# 05_DATA_IO.net
KiCad netlist of a schematic drawn in Altium Designer
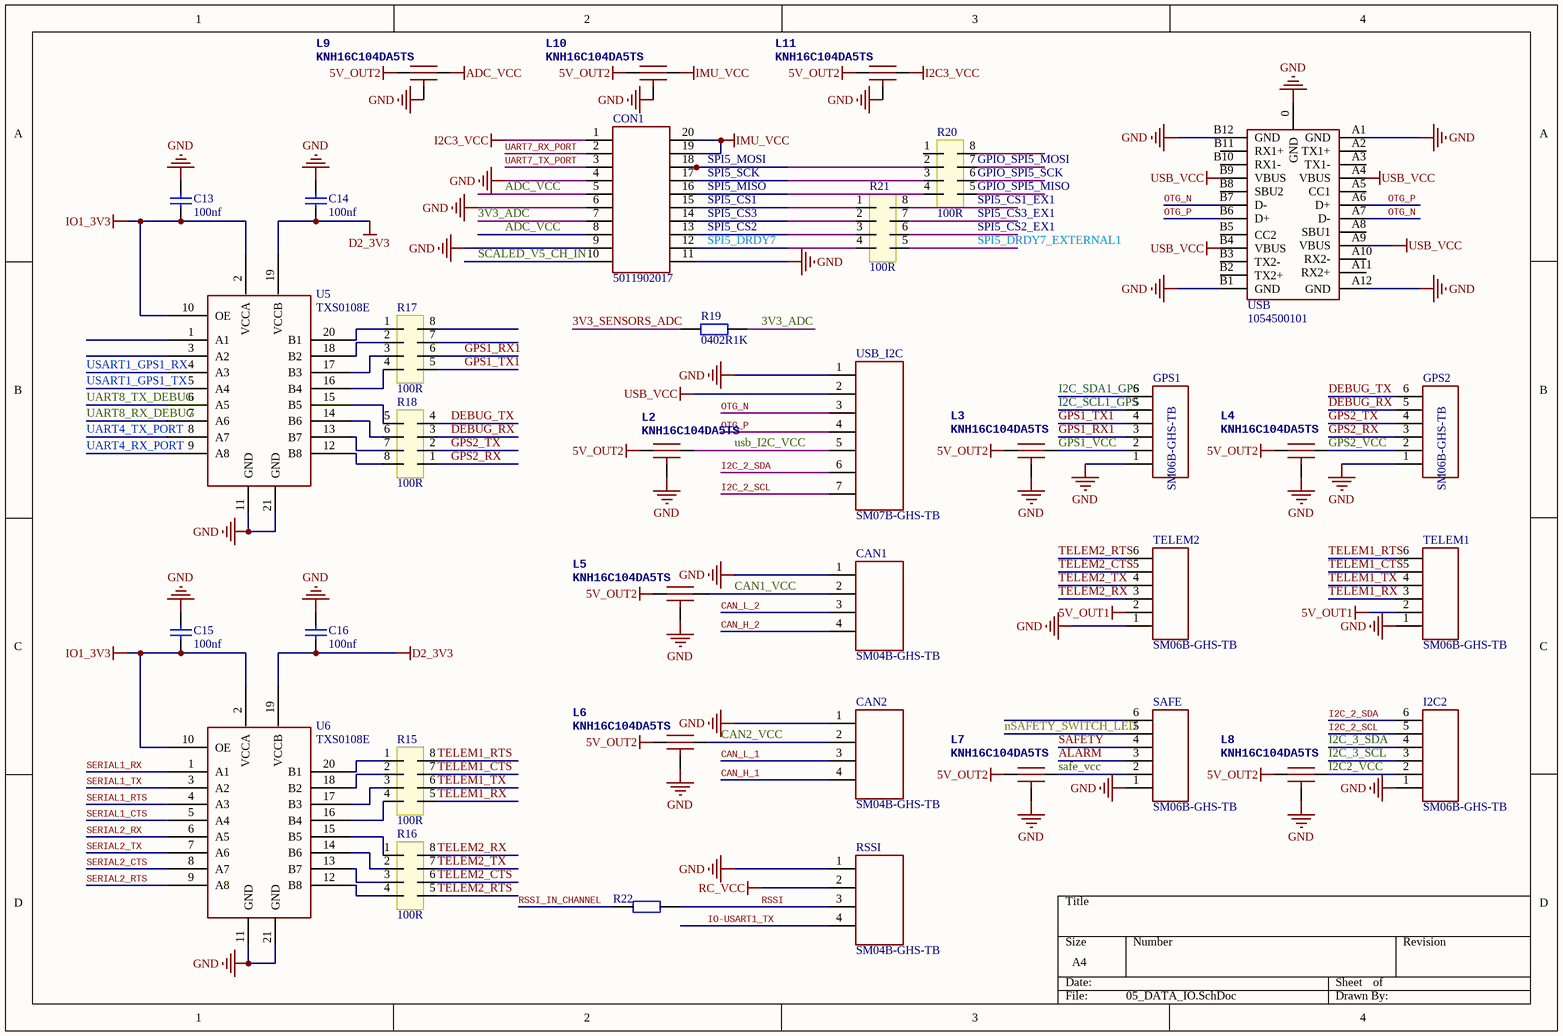
[diagram p0: 05_DATA_IO.SchDoc]

(export (version "E")
  (design (tool "Eeschema 10.0.6"))
  (components
    (comp (ref "C13") (value "100nf") (libsource (lib "Miscellaneous Devices") (part "Cap")))
    (comp (ref "C14") (value "100nf") (libsource (lib "Miscellaneous Devices") (part "Cap")))
    (comp (ref "C15") (value "100nf") (libsource (lib "Miscellaneous Devices") (part "Cap")))
    (comp (ref "C16") (value "100nf") (libsource (lib "Miscellaneous Devices") (part "Cap")))
    (comp (ref "CAN1")
      (value "SM04B-GHS-TB")
      (footprint "BM04B-GHS")
      (libsource (lib "CUAV") (part "SM04B-GHS-TB"))
    )
    (comp (ref "CAN2")
      (value "SM04B-GHS-TB")
      (footprint "BM04B-GHS")
      (libsource (lib "CUAV") (part "SM04B-GHS-TB"))
    )
    (comp (ref "CON1")
      (value "5011902017")
      (footprint "5011902017")
      (libsource (lib "CUAV") (part "5011902017"))
    )
    (comp (ref "GPS1")
      (value "SM06B-GHS-TB")
      (footprint "SM06B-GHS-TB")
      (libsource (lib "CUAV") (part "SM06B-GHS-TB"))
    )
    (comp (ref "GPS2")
      (value "SM06B-GHS-TB")
      (footprint "SM06B-GHS-TB")
      (libsource (lib "CUAV") (part "SM06B-GHS-TB"))
    )
    (comp (ref "I2C2")
      (value "SM06B-GHS-TB")
      (footprint "SM06B-GHS-TB")
      (libsource (lib "CUAV") (part "SM06B-GHS-TB"))
    )
    (comp (ref "L2")
      (value "KNH16C104DA5TS")
      (footprint "KYOCERA-KNH16-DA")
      (description "Capacitor, Filter, 0.1uF, 25V, 2A, 0603, SMD")
      (fields (field (name "3DR_PARTNO") "ECM0719"))
      (libsource (lib "PCA_0005_FULL_CB_REV_A") (part "KNH16C104DA5TS"))
    )
    (comp (ref "L3")
      (value "KNH16C104DA5TS")
      (footprint "KYOCERA-KNH16-DA")
      (description "Capacitor, Filter, 0.1uF, 25V, 2A, 0603, SMD")
      (fields (field (name "3DR_PARTNO") "ECM0719"))
      (libsource (lib "PCA_0005_FULL_CB_REV_A") (part "KNH16C104DA5TS"))
    )
    (comp (ref "L4")
      (value "KNH16C104DA5TS")
      (footprint "KYOCERA-KNH16-DA")
      (description "Capacitor, Filter, 0.1uF, 25V, 2A, 0603, SMD")
      (fields (field (name "3DR_PARTNO") "ECM0719"))
      (libsource (lib "PCA_0005_FULL_CB_REV_A") (part "KNH16C104DA5TS"))
    )
    (comp (ref "L5")
      (value "KNH16C104DA5TS")
      (footprint "KYOCERA-KNH16-DA")
      (description "Capacitor, Filter, 0.1uF, 25V, 2A, 0603, SMD")
      (fields (field (name "3DR_PARTNO") "ECM0719"))
      (libsource (lib "PCA_0005_FULL_CB_REV_A") (part "KNH16C104DA5TS"))
    )
    (comp (ref "L6")
      (value "KNH16C104DA5TS")
      (footprint "KYOCERA-KNH16-DA")
      (description "Capacitor, Filter, 0.1uF, 25V, 2A, 0603, SMD")
      (fields (field (name "3DR_PARTNO") "ECM0719"))
      (libsource (lib "PCA_0005_FULL_CB_REV_A") (part "KNH16C104DA5TS"))
    )
    (comp (ref "L7")
      (value "KNH16C104DA5TS")
      (footprint "KYOCERA-KNH16-DA")
      (description "Capacitor, Filter, 0.1uF, 25V, 2A, 0603, SMD")
      (fields (field (name "3DR_PARTNO") "ECM0719"))
      (libsource (lib "PCA_0005_FULL_CB_REV_A") (part "KNH16C104DA5TS"))
    )
    (comp (ref "L8")
      (value "KNH16C104DA5TS")
      (footprint "KYOCERA-KNH16-DA")
      (description "Capacitor, Filter, 0.1uF, 25V, 2A, 0603, SMD")
      (fields (field (name "3DR_PARTNO") "ECM0719"))
      (libsource (lib "PCA_0005_FULL_CB_REV_A") (part "KNH16C104DA5TS"))
    )
    (comp (ref "L9")
      (value "KNH16C104DA5TS")
      (footprint "KYOCERA-KNH16-DA")
      (description "Capacitor, Filter, 0.1uF, 25V, 2A, 0603, SMD")
      (fields (field (name "3DR_PARTNO") "ECM0719"))
      (libsource (lib "PCA_0005_FULL_CB_REV_A") (part "KNH16C104DA5TS"))
    )
    (comp (ref "L10")
      (value "KNH16C104DA5TS")
      (footprint "KYOCERA-KNH16-DA")
      (description "Capacitor, Filter, 0.1uF, 25V, 2A, 0603, SMD")
      (fields (field (name "3DR_PARTNO") "ECM0719"))
      (libsource (lib "PCA_0005_FULL_CB_REV_A") (part "KNH16C104DA5TS"))
    )
    (comp (ref "L11")
      (value "KNH16C104DA5TS")
      (footprint "KYOCERA-KNH16-DA")
      (description "Capacitor, Filter, 0.1uF, 25V, 2A, 0603, SMD")
      (fields (field (name "3DR_PARTNO") "ECM0719"))
      (libsource (lib "PCA_0005_FULL_CB_REV_A") (part "KNH16C104DA5TS"))
    )
    (comp (ref "R15") (value "100R") (footprint "0402_4r") (libsource (lib "CUAV") (part "0402-8R-4R")))
    (comp (ref "R16") (value "100R") (footprint "0402_4r") (libsource (lib "CUAV") (part "0402-8R-4R")))
    (comp (ref "R17") (value "100R") (footprint "0402_4r") (libsource (lib "CUAV") (part "0402-8R-4R")))
    (comp (ref "R18") (value "100R") (footprint "0402_4r") (libsource (lib "") (part "0402-8R-4R_1")))
    (comp (ref "R19")
      (value "0402R1K")
      (footprint "0402R")
      (description "0402R1K 1%")
      (libsource (lib "CUAV") (part "0402R1K"))
    )
    (comp (ref "R20") (value "100R") (footprint "0402_4r") (libsource (lib "CUAV") (part "0402-8R-4R")))
    (comp (ref "R21") (value "100R") (footprint "0402_4r") (libsource (lib "CUAV") (part "0402-8R-4R")))
    (comp (ref "R22")
      (value "0402R100R")
      (footprint "0402R")
      (description "0402R100R 1%")
      (libsource (lib "CUAV") (part "0402R100R"))
    )
    (comp (ref "RSSI")
      (value "SM04B-GHS-TB")
      (footprint "BM04B-GHS")
      (libsource (lib "CUAV") (part "SM04B-GHS-TB"))
    )
    (comp (ref "SAFE")
      (value "SM06B-GHS-TB")
      (footprint "SM06B-GHS-TB")
      (libsource (lib "CUAV") (part "SM06B-GHS-TB"))
    )
    (comp (ref "TELEM1")
      (value "SM06B-GHS-TB")
      (footprint "SM06B-GHS-TB")
      (libsource (lib "CUAV") (part "SM06B-GHS-TB"))
    )
    (comp (ref "TELEM2")
      (value "SM06B-GHS-TB")
      (footprint "SM06B-GHS-TB")
      (libsource (lib "CUAV") (part "SM06B-GHS-TB"))
    )
    (comp (ref "U5") (value "TXS0108E") (footprint "VQFN20") (libsource (lib "CUAV") (part "TXS0108E")))
    (comp (ref "U6") (value "TXS0108E") (footprint "VQFN20") (libsource (lib "CUAV") (part "TXS0108E")))
    (comp (ref "USB")
      (value "1054500101")
      (footprint "1054500101")
      (libsource (lib "CUAV") (part "1054500101"))
    )
    (comp (ref "USB_I2C")
      (value "SM07B-GHS-TB")
      (footprint "SM07B-GHS-TB")
      (libsource (lib "CUAV") (part "SM07B-GHS-TB"))
    )
  )
  (nets
    (net (code "1") (name "/3V3_ADC") (class "Default")
      (node (ref "CON1") (pin "7") (pintype "passive"))
      (node (ref "R19") (pin "2") (pintype "passive"))
    )
    (net (code "2") (name "/3V3_SENSORS_ADC") (class "Default")
      (node (ref "R19") (pin "1") (pintype "passive"))
    )
    (net (code "3") (name "/ALARM") (class "Default") (node (ref "SAFE") (pin "3") (pintype "passive")))
    (net (code "4") (name "/CAN1_VCC") (class "Default")
      (node (ref "CAN1") (pin "2") (pintype "passive"))
      (node (ref "L5") (pin "P$2") (pinfunction "P$2_P$2") (pintype "passive"))
    )
    (net (code "5") (name "/CAN2_VCC") (class "Default")
      (node (ref "CAN2") (pin "2") (pintype "passive"))
      (node (ref "L6") (pin "P$2") (pinfunction "P$2_P$2") (pintype "passive"))
    )
    (net (code "6") (name "/CAN_H_1") (class "Default") (node (ref "CAN2") (pin "4") (pintype "passive")))
    (net (code "7") (name "/CAN_H_2") (class "Default") (node (ref "CAN1") (pin "4") (pintype "passive")))
    (net (code "8") (name "/CAN_L_1") (class "Default") (node (ref "CAN2") (pin "3") (pintype "passive")))
    (net (code "9") (name "/CAN_L_2") (class "Default") (node (ref "CAN1") (pin "3") (pintype "passive")))
    (net (code "10") (name "/DEBUG_RX") (class "Default")
      (node (ref "GPS2") (pin "5") (pintype "passive"))
      (node (ref "R18") (pin "3") (pinfunction "3_3") (pintype "passive"))
    )
    (net (code "11") (name "/DEBUG_TX") (class "Default")
      (node (ref "GPS2") (pin "6") (pintype "passive"))
      (node (ref "R18") (pin "4") (pinfunction "4_4") (pintype "passive"))
    )
    (net (code "12") (name "/GPIO_SPI5_MISO") (class "Default")
      (node (ref "R20") (pin "5") (pinfunction "5_5") (pintype "passive"))
    )
    (net (code "13") (name "/GPIO_SPI5_MOSI") (class "Default")
      (node (ref "R20") (pin "7") (pinfunction "7_7") (pintype "passive"))
    )
    (net (code "14") (name "/GPIO_SPI5_SCK") (class "Default")
      (node (ref "R20") (pin "6") (pinfunction "6_6") (pintype "passive"))
    )
    (net (code "15") (name "/GPS1_RX1") (class "Default")
      (node (ref "GPS1") (pin "3") (pintype "passive"))
      (node (ref "R17") (pin "6") (pinfunction "6_6") (pintype "passive"))
    )
    (net (code "16") (name "/GPS1_TX1") (class "Default")
      (node (ref "GPS1") (pin "4") (pintype "passive"))
      (node (ref "R17") (pin "5") (pinfunction "5_5") (pintype "passive"))
    )
    (net (code "17") (name "/GPS1_VCC") (class "Default")
      (node (ref "GPS1") (pin "2") (pintype "passive"))
      (node (ref "L3") (pin "P$2") (pinfunction "P$2_P$2") (pintype "passive"))
    )
    (net (code "18") (name "/GPS2_RX") (class "Default")
      (node (ref "GPS2") (pin "3") (pintype "passive"))
      (node (ref "R18") (pin "1") (pinfunction "1_1") (pintype "passive"))
    )
    (net (code "19") (name "/GPS2_TX") (class "Default")
      (node (ref "GPS2") (pin "4") (pintype "passive"))
      (node (ref "R18") (pin "2") (pinfunction "2_2") (pintype "passive"))
    )
    (net (code "20") (name "/GPS2_VCC") (class "Default")
      (node (ref "GPS2") (pin "2") (pintype "passive"))
      (node (ref "L4") (pin "P$2") (pinfunction "P$2_P$2") (pintype "passive"))
    )
    (net (code "21") (name "/I2C2_VCC") (class "Default")
      (node (ref "I2C2") (pin "2") (pintype "passive"))
      (node (ref "L8") (pin "P$2") (pinfunction "P$2_P$2") (pintype "passive"))
    )
    (net (code "22") (name "/I2C_2_SCL") (class "Default")
      (node (ref "I2C2") (pin "5") (pintype "passive"))
      (node (ref "USB_I2C") (pin "7") (pintype "passive"))
    )
    (net (code "23") (name "/I2C_2_SDA") (class "Default")
      (node (ref "I2C2") (pin "6") (pintype "passive"))
      (node (ref "USB_I2C") (pin "6") (pintype "passive"))
    )
    (net (code "24") (name "/I2C_3_SCL") (class "Default") (node (ref "I2C2") (pin "3") (pintype "passive")))
    (net (code "25") (name "/I2C_3_SDA") (class "Default") (node (ref "I2C2") (pin "4") (pintype "passive")))
    (net (code "26") (name "/I2C_SCL1_GPS") (class "Default")
      (node (ref "GPS1") (pin "5") (pintype "passive"))
    )
    (net (code "27") (name "/I2C_SDA1_GPS") (class "Default")
      (node (ref "GPS1") (pin "6") (pintype "passive"))
    )
    (net (code "28") (name "/IO-USART1_TX") (class "Default")
      (node (ref "RSSI") (pin "4") (pintype "passive"))
    )
    (net (code "29") (name "/OTG_N") (class "Default")
      (node (ref "USB") (pin "A7") (pinfunction "D-_A7") (pintype "passive"))
      (node (ref "USB") (pin "B7") (pinfunction "D-_B7") (pintype "passive"))
      (node (ref "USB_I2C") (pin "3") (pintype "passive"))
    )
    (net (code "30") (name "/OTG_P") (class "Default")
      (node (ref "USB") (pin "A6") (pinfunction "D+_A6") (pintype "passive"))
      (node (ref "USB") (pin "B6") (pinfunction "D+_B6") (pintype "passive"))
      (node (ref "USB_I2C") (pin "4") (pintype "passive"))
    )
    (net (code "31") (name "/RSSI") (class "Default")
      (node (ref "R22") (pin "2") (pintype "passive"))
      (node (ref "RSSI") (pin "3") (pintype "passive"))
    )
    (net (code "32") (name "/RSSI_IN_CHANNEL") (class "Default")
      (node (ref "R22") (pin "1") (pintype "passive"))
    )
    (net (code "33") (name "/SAFETY") (class "Default") (node (ref "SAFE") (pin "4") (pintype "passive")))
    (net (code "34") (name "/SCALED_V5_CH_IN") (class "Default")
      (node (ref "CON1") (pin "10") (pintype "passive"))
    )
    (net (code "35") (name "/SERIAL1_CTS") (class "Default")
      (node (ref "U6") (pin "5") (pinfunction "A4_5") (pintype "passive"))
    )
    (net (code "36") (name "/SERIAL1_RTS") (class "Default")
      (node (ref "U6") (pin "4") (pinfunction "A3_4") (pintype "passive"))
    )
    (net (code "37") (name "/SERIAL1_RX") (class "Default")
      (node (ref "U6") (pin "1") (pinfunction "A1_1") (pintype "passive"))
    )
    (net (code "38") (name "/SERIAL1_TX") (class "Default")
      (node (ref "U6") (pin "3") (pinfunction "A2_3") (pintype "passive"))
    )
    (net (code "39") (name "/SERIAL2_CTS") (class "Default")
      (node (ref "U6") (pin "8") (pinfunction "A7_8") (pintype "passive"))
    )
    (net (code "40") (name "/SERIAL2_RTS") (class "Default")
      (node (ref "U6") (pin "9") (pinfunction "A8_9") (pintype "passive"))
    )
    (net (code "41") (name "/SERIAL2_RX") (class "Default")
      (node (ref "U6") (pin "6") (pinfunction "A5_6") (pintype "passive"))
    )
    (net (code "42") (name "/SERIAL2_TX") (class "Default")
      (node (ref "U6") (pin "7") (pinfunction "A6_7") (pintype "passive"))
    )
    (net (code "43") (name "/SPI5_CS1") (class "Default")
      (node (ref "CON1") (pin "15") (pintype "passive"))
      (node (ref "R21") (pin "1") (pinfunction "1_1") (pintype "passive"))
    )
    (net (code "44") (name "/SPI5_CS1_EX1") (class "Default")
      (node (ref "R21") (pin "8") (pinfunction "8_8") (pintype "passive"))
    )
    (net (code "45") (name "/SPI5_CS2") (class "Default")
      (node (ref "CON1") (pin "13") (pintype "passive"))
      (node (ref "R21") (pin "3") (pinfunction "3_3") (pintype "passive"))
    )
    (net (code "46") (name "/SPI5_CS2_EX1") (class "Default")
      (node (ref "R21") (pin "6") (pinfunction "6_6") (pintype "passive"))
    )
    (net (code "47") (name "/SPI5_CS3") (class "Default")
      (node (ref "CON1") (pin "14") (pintype "passive"))
      (node (ref "R21") (pin "2") (pinfunction "2_2") (pintype "passive"))
    )
    (net (code "48") (name "/SPI5_CS3_EX1") (class "Default")
      (node (ref "R21") (pin "7") (pinfunction "7_7") (pintype "passive"))
    )
    (net (code "49") (name "/SPI5_DRDY7") (class "Default")
      (node (ref "CON1") (pin "12") (pintype "passive"))
      (node (ref "R21") (pin "4") (pinfunction "4_4") (pintype "passive"))
    )
    (net (code "50") (name "/SPI5_DRDY7_EXTERNAL1") (class "Default")
      (node (ref "R21") (pin "5") (pinfunction "5_5") (pintype "passive"))
    )
    (net (code "51") (name "/SPI5_MISO") (class "Default")
      (node (ref "CON1") (pin "16") (pintype "passive"))
      (node (ref "R20") (pin "4") (pinfunction "4_4") (pintype "passive"))
    )
    (net (code "52") (name "/SPI5_MOSI") (class "Default")
      (node (ref "CON1") (pin "18") (pintype "passive"))
      (node (ref "R20") (pin "2") (pinfunction "2_2") (pintype "passive"))
    )
    (net (code "53") (name "/SPI5_SCK") (class "Default")
      (node (ref "CON1") (pin "17") (pintype "passive"))
      (node (ref "R20") (pin "3") (pinfunction "3_3") (pintype "passive"))
    )
    (net (code "54") (name "/TELEM1_CTS") (class "Default")
      (node (ref "R15") (pin "7") (pinfunction "7_7") (pintype "passive"))
      (node (ref "TELEM1") (pin "5") (pintype "passive"))
    )
    (net (code "55") (name "/TELEM1_RTS") (class "Default")
      (node (ref "R15") (pin "8") (pinfunction "8_8") (pintype "passive"))
      (node (ref "TELEM1") (pin "6") (pintype "passive"))
    )
    (net (code "56") (name "/TELEM1_RX") (class "Default")
      (node (ref "R15") (pin "5") (pinfunction "5_5") (pintype "passive"))
      (node (ref "TELEM1") (pin "3") (pintype "passive"))
    )
    (net (code "57") (name "/TELEM1_TX") (class "Default")
      (node (ref "R15") (pin "6") (pinfunction "6_6") (pintype "passive"))
      (node (ref "TELEM1") (pin "4") (pintype "passive"))
    )
    (net (code "58") (name "/TELEM2_CTS") (class "Default")
      (node (ref "R16") (pin "6") (pinfunction "6_6") (pintype "passive"))
      (node (ref "TELEM2") (pin "5") (pintype "passive"))
    )
    (net (code "59") (name "/TELEM2_RTS") (class "Default")
      (node (ref "R16") (pin "5") (pinfunction "5_5") (pintype "passive"))
      (node (ref "TELEM2") (pin "6") (pintype "passive"))
    )
    (net (code "60") (name "/TELEM2_RX") (class "Default")
      (node (ref "R16") (pin "8") (pinfunction "8_8") (pintype "passive"))
      (node (ref "TELEM2") (pin "3") (pintype "passive"))
    )
    (net (code "61") (name "/TELEM2_TX") (class "Default")
      (node (ref "R16") (pin "7") (pinfunction "7_7") (pintype "passive"))
      (node (ref "TELEM2") (pin "4") (pintype "passive"))
    )
    (net (code "62") (name "/UART4_RX_PORT") (class "Default")
      (node (ref "U5") (pin "9") (pinfunction "A8_9") (pintype "passive"))
    )
    (net (code "63") (name "/UART4_TX_PORT") (class "Default")
      (node (ref "U5") (pin "8") (pinfunction "A7_8") (pintype "passive"))
    )
    (net (code "64") (name "/UART7_RX_PORT") (class "Default")
      (node (ref "CON1") (pin "2") (pintype "passive"))
    )
    (net (code "65") (name "/UART7_TX_PORT") (class "Default")
      (node (ref "CON1") (pin "3") (pintype "passive"))
    )
    (net (code "66") (name "/UART8_RX_DEBUG") (class "Default")
      (node (ref "U5") (pin "7") (pinfunction "A6_7") (pintype "passive"))
    )
    (net (code "67") (name "/UART8_TX_DEBUG") (class "Default")
      (node (ref "U5") (pin "6") (pinfunction "A5_6") (pintype "passive"))
    )
    (net (code "68") (name "/USART1_GPS1_RX") (class "Default")
      (node (ref "U5") (pin "4") (pinfunction "A3_4") (pintype "passive"))
    )
    (net (code "69") (name "/USART1_GPS1_TX") (class "Default")
      (node (ref "U5") (pin "5") (pinfunction "A4_5") (pintype "passive"))
    )
    (net (code "70") (name "/nSAFETY_SWITCH_LED") (class "Default")
      (node (ref "SAFE") (pin "5") (pintype "passive"))
    )
    (net (code "71") (name "/safe_vcc") (class "Default")
      (node (ref "L7") (pin "P$2") (pinfunction "P$2_P$2") (pintype "passive"))
      (node (ref "SAFE") (pin "2") (pintype "passive"))
    )
    (net (code "72") (name "/usb_I2C_VCC") (class "Default")
      (node (ref "L2") (pin "P$2") (pinfunction "P$2_P$2") (pintype "passive"))
      (node (ref "USB_I2C") (pin "5") (pintype "passive"))
    )
    (net (code "73") (name "5V_OUT1") (class "Default")
      (node (ref "TELEM1") (pin "2") (pintype "passive"))
      (node (ref "TELEM2") (pin "2") (pintype "passive"))
    )
    (net (code "74") (name "5V_OUT2") (class "Default")
      (node (ref "L10") (pin "P$1") (pinfunction "P$1_P$1") (pintype "passive"))
      (node (ref "L11") (pin "P$1") (pinfunction "P$1_P$1") (pintype "passive"))
      (node (ref "L2") (pin "P$1") (pinfunction "P$1_P$1") (pintype "passive"))
      (node (ref "L3") (pin "P$1") (pinfunction "P$1_P$1") (pintype "passive"))
      (node (ref "L4") (pin "P$1") (pinfunction "P$1_P$1") (pintype "passive"))
      (node (ref "L5") (pin "P$1") (pinfunction "P$1_P$1") (pintype "passive"))
      (node (ref "L6") (pin "P$1") (pinfunction "P$1_P$1") (pintype "passive"))
      (node (ref "L7") (pin "P$1") (pinfunction "P$1_P$1") (pintype "passive"))
      (node (ref "L8") (pin "P$1") (pinfunction "P$1_P$1") (pintype "passive"))
      (node (ref "L9") (pin "P$1") (pinfunction "P$1_P$1") (pintype "passive"))
    )
    (net (code "75") (name "ADC_VCC") (class "Default")
      (node (ref "CON1") (pin "5") (pintype "passive"))
      (node (ref "CON1") (pin "8") (pintype "passive"))
      (node (ref "L9") (pin "P$2") (pinfunction "P$2_P$2") (pintype "passive"))
    )
    (net (code "76") (name "D2_3V3") (class "Default")
      (node (ref "C14") (pin "2") (pinfunction "2_2") (pintype "passive"))
      (node (ref "C16") (pin "2") (pinfunction "2_2") (pintype "passive"))
      (node (ref "U5") (pin "19") (pinfunction "VCCB_19") (pintype "passive"))
      (node (ref "U6") (pin "19") (pinfunction "VCCB_19") (pintype "passive"))
    )
    (net (code "77") (name "GND") (class "Default")
      (node (ref "C13") (pin "1") (pinfunction "1_1") (pintype "passive"))
      (node (ref "C14") (pin "1") (pinfunction "1_1") (pintype "passive"))
      (node (ref "C15") (pin "1") (pinfunction "1_1") (pintype "passive"))
      (node (ref "C16") (pin "1") (pinfunction "1_1") (pintype "passive"))
      (node (ref "CAN1") (pin "1") (pintype "passive"))
      (node (ref "CAN2") (pin "1") (pintype "passive"))
      (node (ref "CON1") (pin "11") (pintype "passive"))
      (node (ref "CON1") (pin "4") (pintype "passive"))
      (node (ref "CON1") (pin "6") (pintype "passive"))
      (node (ref "CON1") (pin "9") (pintype "passive"))
      (node (ref "GPS1") (pin "1") (pintype "passive"))
      (node (ref "GPS2") (pin "1") (pintype "passive"))
      (node (ref "I2C2") (pin "1") (pintype "passive"))
      (node (ref "L10") (pin "GND") (pinfunction "GND_GND") (pintype "passive"))
      (node (ref "L11") (pin "GND") (pinfunction "GND_GND") (pintype "passive"))
      (node (ref "L2") (pin "GND") (pinfunction "GND_GND") (pintype "passive"))
      (node (ref "L3") (pin "GND") (pinfunction "GND_GND") (pintype "passive"))
      (node (ref "L4") (pin "GND") (pinfunction "GND_GND") (pintype "passive"))
      (node (ref "L5") (pin "GND") (pinfunction "GND_GND") (pintype "passive"))
      (node (ref "L6") (pin "GND") (pinfunction "GND_GND") (pintype "passive"))
      (node (ref "L7") (pin "GND") (pinfunction "GND_GND") (pintype "passive"))
      (node (ref "L8") (pin "GND") (pinfunction "GND_GND") (pintype "passive"))
      (node (ref "L9") (pin "GND") (pinfunction "GND_GND") (pintype "passive"))
      (node (ref "RSSI") (pin "1") (pintype "passive"))
      (node (ref "SAFE") (pin "1") (pintype "passive"))
      (node (ref "TELEM1") (pin "1") (pintype "passive"))
      (node (ref "TELEM2") (pin "1") (pintype "passive"))
      (node (ref "U5") (pin "11") (pinfunction "GND_11") (pintype "passive"))
      (node (ref "U5") (pin "21") (pinfunction "GND_21") (pintype "passive"))
      (node (ref "U6") (pin "11") (pinfunction "GND_11") (pintype "passive"))
      (node (ref "U6") (pin "21") (pinfunction "GND_21") (pintype "passive"))
      (node (ref "USB") (pin "0") (pinfunction "GND_0") (pintype "passive"))
      (node (ref "USB") (pin "A1") (pinfunction "GND_A1") (pintype "passive"))
      (node (ref "USB") (pin "A12") (pinfunction "GND_A12") (pintype "passive"))
      (node (ref "USB") (pin "B1") (pinfunction "GND_B1") (pintype "passive"))
      (node (ref "USB") (pin "B12") (pinfunction "GND_B12") (pintype "passive"))
      (node (ref "USB_I2C") (pin "1") (pintype "passive"))
    )
    (net (code "78") (name "I2C3_VCC") (class "Default")
      (node (ref "CON1") (pin "1") (pintype "passive"))
      (node (ref "L11") (pin "P$2") (pinfunction "P$2_P$2") (pintype "passive"))
    )
    (net (code "79") (name "IMU_VCC") (class "Default")
      (node (ref "CON1") (pin "19") (pintype "passive"))
      (node (ref "CON1") (pin "20") (pintype "passive"))
      (node (ref "L10") (pin "P$2") (pinfunction "P$2_P$2") (pintype "passive"))
    )
    (net (code "80") (name "IO1_3V3") (class "Default")
      (node (ref "C13") (pin "2") (pinfunction "2_2") (pintype "passive"))
      (node (ref "C15") (pin "2") (pinfunction "2_2") (pintype "passive"))
      (node (ref "U5") (pin "10") (pinfunction "OE_10") (pintype "passive"))
      (node (ref "U5") (pin "2") (pinfunction "VCCA_2") (pintype "passive"))
      (node (ref "U6") (pin "10") (pinfunction "OE_10") (pintype "passive"))
      (node (ref "U6") (pin "2") (pinfunction "VCCA_2") (pintype "passive"))
    )
    (net (code "81") (name "Net-(U5-B1)") (class "Default")
      (node (ref "R17") (pin "1") (pinfunction "1_1") (pintype "passive"))
      (node (ref "U5") (pin "20") (pinfunction "B1_20") (pintype "passive"))
    )
    (net (code "82") (name "Net-(U5-B2)") (class "Default")
      (node (ref "R17") (pin "2") (pinfunction "2_2") (pintype "passive"))
      (node (ref "U5") (pin "18") (pinfunction "B2_18") (pintype "passive"))
    )
    (net (code "83") (name "Net-(U5-B3)") (class "Default")
      (node (ref "R17") (pin "3") (pinfunction "3_3") (pintype "passive"))
      (node (ref "U5") (pin "17") (pinfunction "B3_17") (pintype "passive"))
    )
    (net (code "84") (name "Net-(U5-B4)") (class "Default")
      (node (ref "R17") (pin "4") (pinfunction "4_4") (pintype "passive"))
      (node (ref "U5") (pin "16") (pinfunction "B4_16") (pintype "passive"))
    )
    (net (code "85") (name "Net-(U5-B5)") (class "Default")
      (node (ref "R18") (pin "5") (pinfunction "5_5") (pintype "passive"))
      (node (ref "U5") (pin "15") (pinfunction "B5_15") (pintype "passive"))
    )
    (net (code "86") (name "Net-(U5-B6)") (class "Default")
      (node (ref "R18") (pin "6") (pinfunction "6_6") (pintype "passive"))
      (node (ref "U5") (pin "14") (pinfunction "B6_14") (pintype "passive"))
    )
    (net (code "87") (name "Net-(U5-B7)") (class "Default")
      (node (ref "R18") (pin "7") (pinfunction "7_7") (pintype "passive"))
      (node (ref "U5") (pin "13") (pinfunction "B7_13") (pintype "passive"))
    )
    (net (code "88") (name "Net-(U5-B8)") (class "Default")
      (node (ref "R18") (pin "8") (pinfunction "8_8") (pintype "passive"))
      (node (ref "U5") (pin "12") (pinfunction "B8_12") (pintype "passive"))
    )
    (net (code "89") (name "Net-(U6-B1)") (class "Default")
      (node (ref "R15") (pin "1") (pinfunction "1_1") (pintype "passive"))
      (node (ref "U6") (pin "20") (pinfunction "B1_20") (pintype "passive"))
    )
    (net (code "90") (name "Net-(U6-B2)") (class "Default")
      (node (ref "R15") (pin "2") (pinfunction "2_2") (pintype "passive"))
      (node (ref "U6") (pin "18") (pinfunction "B2_18") (pintype "passive"))
    )
    (net (code "91") (name "Net-(U6-B3)") (class "Default")
      (node (ref "R15") (pin "3") (pinfunction "3_3") (pintype "passive"))
      (node (ref "U6") (pin "17") (pinfunction "B3_17") (pintype "passive"))
    )
    (net (code "92") (name "Net-(U6-B4)") (class "Default")
      (node (ref "R15") (pin "4") (pinfunction "4_4") (pintype "passive"))
      (node (ref "U6") (pin "16") (pinfunction "B4_16") (pintype "passive"))
    )
    (net (code "93") (name "Net-(U6-B5)") (class "Default")
      (node (ref "R16") (pin "1") (pinfunction "1_1") (pintype "passive"))
      (node (ref "U6") (pin "15") (pinfunction "B5_15") (pintype "passive"))
    )
    (net (code "94") (name "Net-(U6-B6)") (class "Default")
      (node (ref "R16") (pin "2") (pinfunction "2_2") (pintype "passive"))
      (node (ref "U6") (pin "14") (pinfunction "B6_14") (pintype "passive"))
    )
    (net (code "95") (name "Net-(U6-B7)") (class "Default")
      (node (ref "R16") (pin "3") (pinfunction "3_3") (pintype "passive"))
      (node (ref "U6") (pin "13") (pinfunction "B7_13") (pintype "passive"))
    )
    (net (code "96") (name "Net-(U6-B8)") (class "Default")
      (node (ref "R16") (pin "4") (pinfunction "4_4") (pintype "passive"))
      (node (ref "U6") (pin "12") (pinfunction "B8_12") (pintype "passive"))
    )
    (net (code "97") (name "RC_VCC") (class "Default") (node (ref "RSSI") (pin "2") (pintype "passive")))
    (net (code "98") (name "USB_VCC") (class "Default")
      (node (ref "USB") (pin "A4") (pinfunction "VBUS_A4") (pintype "passive"))
      (node (ref "USB") (pin "A9") (pinfunction "VBUS_A9") (pintype "passive"))
      (node (ref "USB") (pin "B4") (pinfunction "VBUS_B4") (pintype "passive"))
      (node (ref "USB") (pin "B9") (pinfunction "VBUS_B9") (pintype "passive"))
      (node (ref "USB_I2C") (pin "2") (pintype "passive"))
    )
    (net (code "99") (name "unconnected-(R17-Pad7)") (class "Default")
      (node (ref "R17") (pin "7") (pinfunction "7_7") (pintype "passive"))
    )
    (net (code "100") (name "unconnected-(R17-Pad8)") (class "Default")
      (node (ref "R17") (pin "8") (pinfunction "8_8") (pintype "passive"))
    )
    (net (code "101") (name "unconnected-(R20-Pad1)") (class "Default")
      (node (ref "R20") (pin "1") (pinfunction "1_1") (pintype "passive"))
    )
    (net (code "102") (name "unconnected-(R20-Pad8)") (class "Default")
      (node (ref "R20") (pin "8") (pinfunction "8_8") (pintype "passive"))
    )
    (net (code "103") (name "unconnected-(SAFE-Pad6)") (class "Default")
      (node (ref "SAFE") (pin "6") (pintype "passive"))
    )
    (net (code "104") (name "unconnected-(U5-A1-Pad1)") (class "Default")
      (node (ref "U5") (pin "1") (pinfunction "A1_1") (pintype "passive"))
    )
    (net (code "105") (name "unconnected-(U5-A2-Pad3)") (class "Default")
      (node (ref "U5") (pin "3") (pinfunction "A2_3") (pintype "passive"))
    )
    (net (code "106") (name "unconnected-(USB-CC1-PadA5)") (class "Default")
      (node (ref "USB") (pin "A5") (pinfunction "CC1_A5") (pintype "passive"))
    )
    (net (code "107") (name "unconnected-(USB-CC2-PadB5)") (class "Default")
      (node (ref "USB") (pin "B5") (pinfunction "CC2_B5") (pintype "passive"))
    )
    (net (code "108") (name "unconnected-(USB-RX1+-PadB11)") (class "Default")
      (node (ref "USB") (pin "B11") (pinfunction "RX1+_B11") (pintype "passive"))
    )
    (net (code "109") (name "unconnected-(USB-RX1--PadB10)") (class "Default")
      (node (ref "USB") (pin "B10") (pinfunction "RX1-_B10") (pintype "passive"))
    )
    (net (code "110") (name "unconnected-(USB-RX2+-PadA11)") (class "Default")
      (node (ref "USB") (pin "A11") (pinfunction "RX2+_A11") (pintype "passive"))
    )
    (net (code "111") (name "unconnected-(USB-RX2--PadA10)") (class "Default")
      (node (ref "USB") (pin "A10") (pinfunction "RX2-_A10") (pintype "passive"))
    )
    (net (code "112") (name "unconnected-(USB-SBU1-PadA8)") (class "Default")
      (node (ref "USB") (pin "A8") (pinfunction "SBU1_A8") (pintype "passive"))
    )
    (net (code "113") (name "unconnected-(USB-SBU2-PadB8)") (class "Default")
      (node (ref "USB") (pin "B8") (pinfunction "SBU2_B8") (pintype "passive"))
    )
    (net (code "114") (name "unconnected-(USB-TX1+-PadA2)") (class "Default")
      (node (ref "USB") (pin "A2") (pinfunction "TX1+_A2") (pintype "passive"))
    )
    (net (code "115") (name "unconnected-(USB-TX1--PadA3)") (class "Default")
      (node (ref "USB") (pin "A3") (pinfunction "TX1-_A3") (pintype "passive"))
    )
    (net (code "116") (name "unconnected-(USB-TX2+-PadB2)") (class "Default")
      (node (ref "USB") (pin "B2") (pinfunction "TX2+_B2") (pintype "passive"))
    )
    (net (code "117") (name "unconnected-(USB-TX2--PadB3)") (class "Default")
      (node (ref "USB") (pin "B3") (pinfunction "TX2-_B3") (pintype "passive"))
    )
  )
)
